# Access_Control_Passive_Splitter.net
KiCad netlist of a schematic drawn in EasyEDA Pro
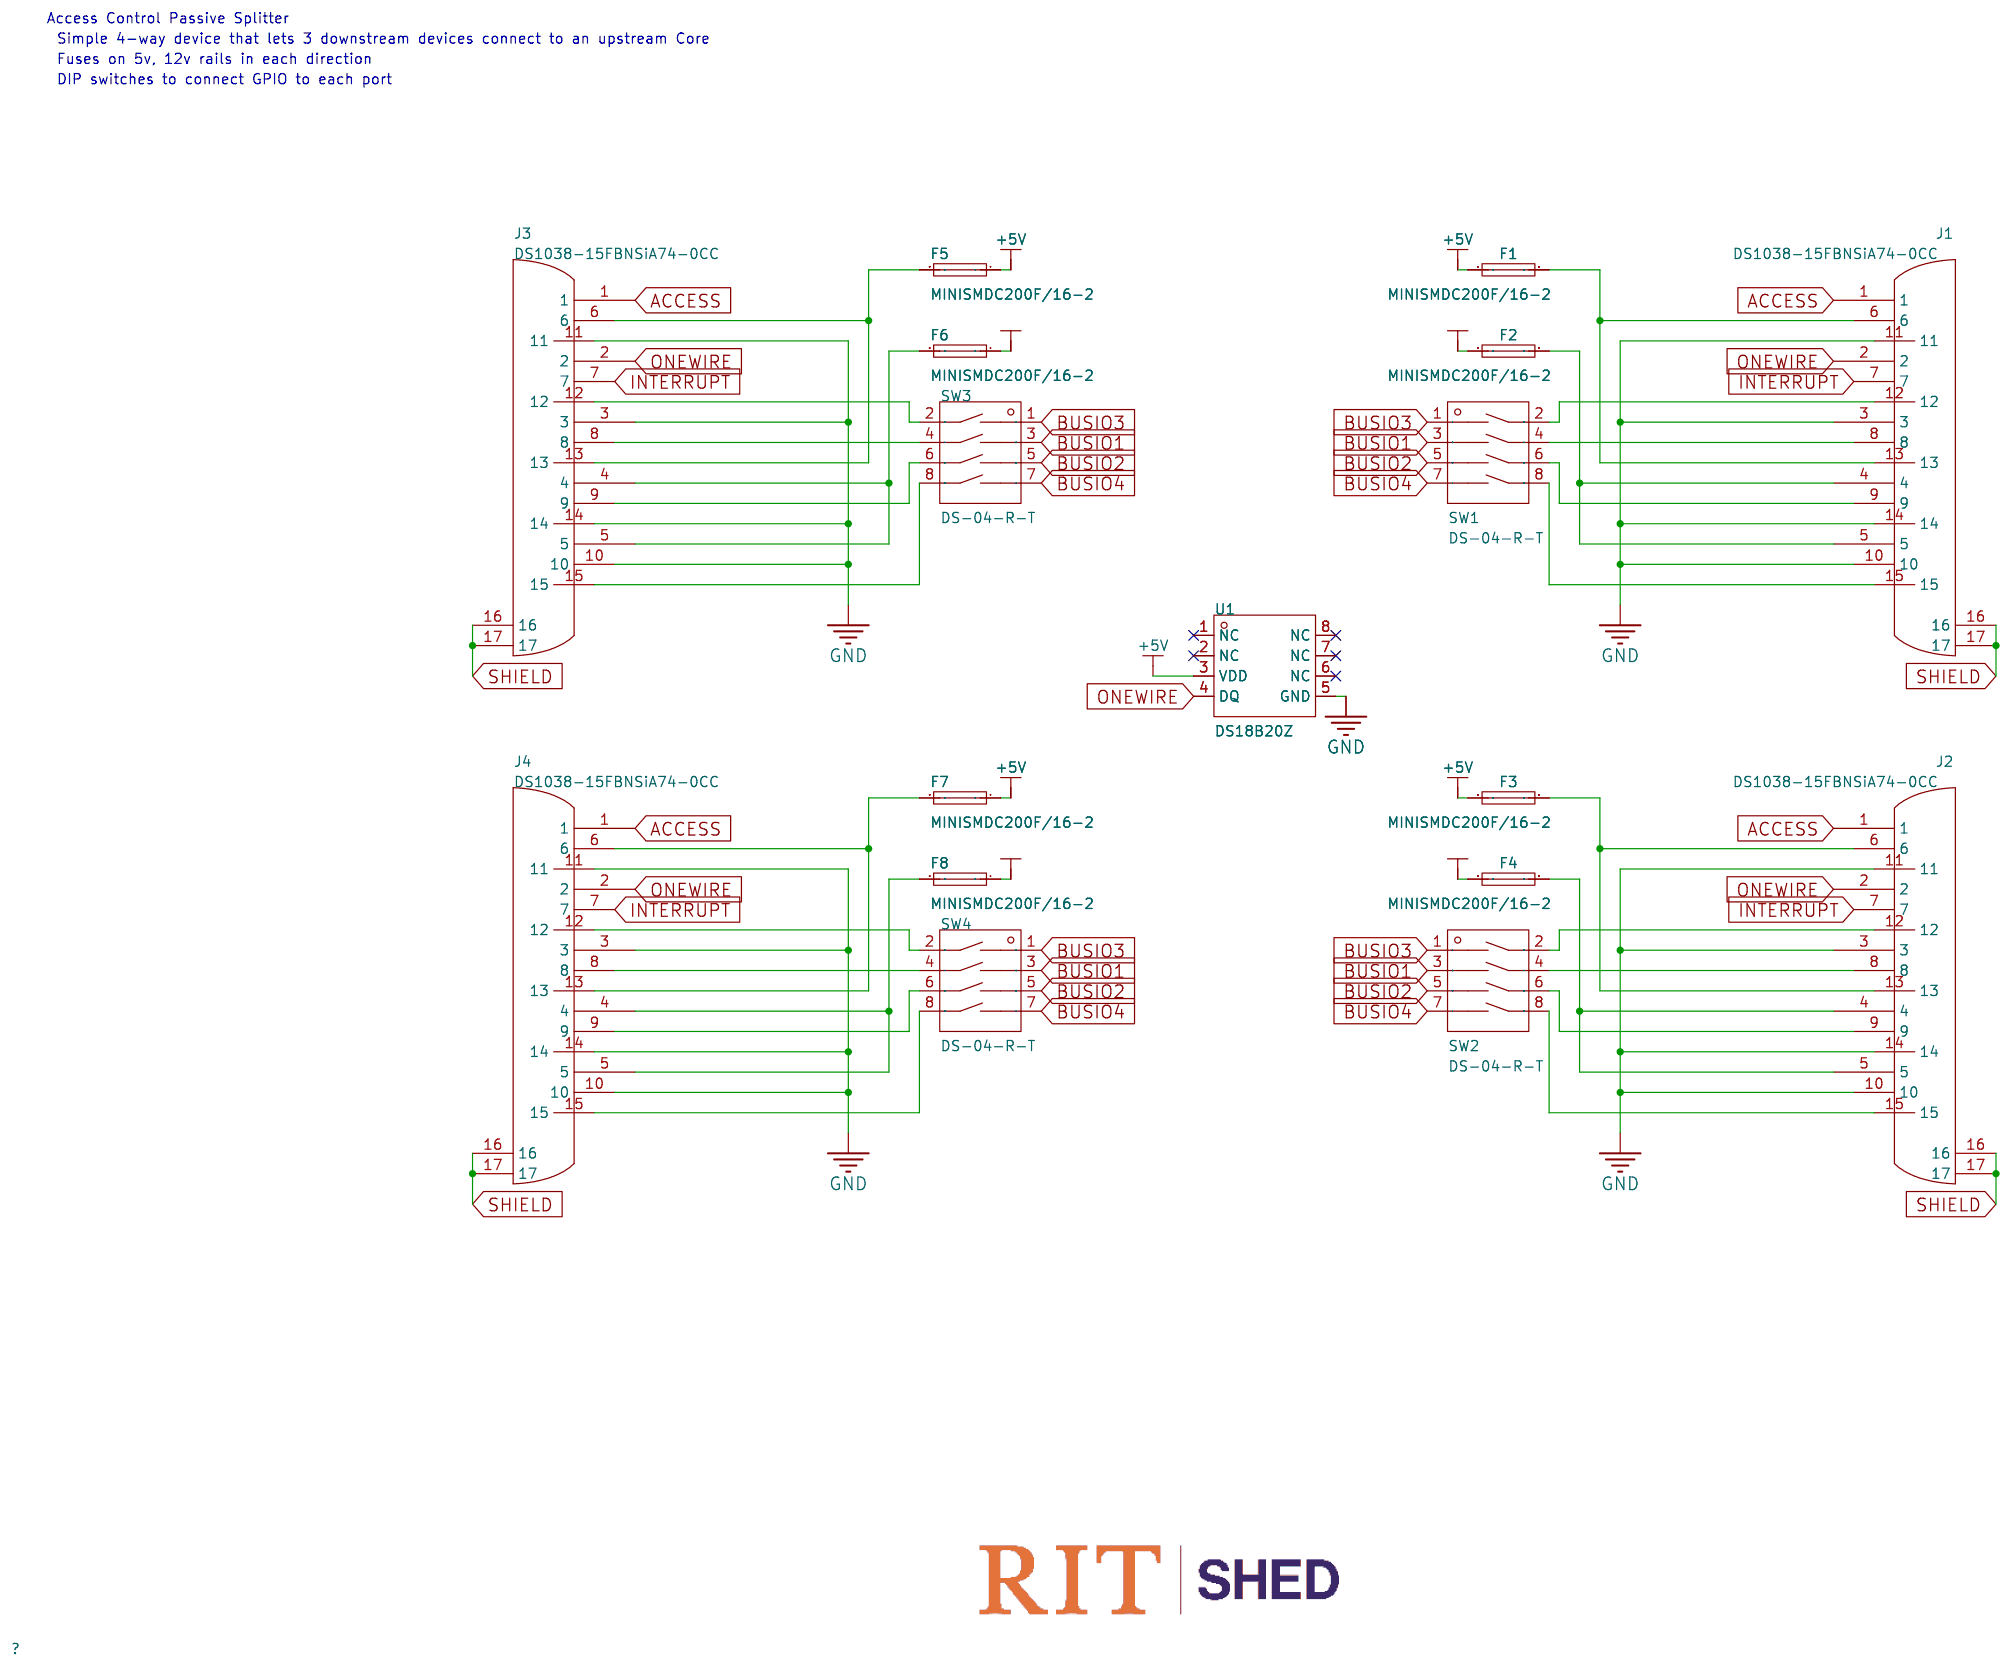
[diagram p0: schematic sheet]

(export (version "E")
  (design (tool "Eeschema 10.0.6"))
  (components
    (comp (ref "F1")
      (value "MINISMDC200F/16-2")
      (footprint "easyedapro:R1812")
      (fields (field (name "Manufacturer") "Littelfuse(美国力特)"))
      (libsource (lib "easyedapro") (part "MINISMDC200F/16-2"))
    )
    (comp (ref "F2")
      (value "MINISMDC200F/16-2")
      (footprint "easyedapro:R1812")
      (fields (field (name "Manufacturer") "Littelfuse(美国力特)"))
      (libsource (lib "easyedapro") (part "MINISMDC200F/16-2"))
    )
    (comp (ref "F3")
      (value "MINISMDC200F/16-2")
      (footprint "easyedapro:R1812")
      (fields (field (name "Manufacturer") "Littelfuse(美国力特)"))
      (libsource (lib "easyedapro") (part "MINISMDC200F/16-2"))
    )
    (comp (ref "F4")
      (value "MINISMDC200F/16-2")
      (footprint "easyedapro:R1812")
      (fields (field (name "Manufacturer") "Littelfuse(美国力特)"))
      (libsource (lib "easyedapro") (part "MINISMDC200F/16-2"))
    )
    (comp (ref "F5")
      (value "MINISMDC200F/16-2")
      (footprint "easyedapro:R1812")
      (fields (field (name "Manufacturer") "Littelfuse(美国力特)"))
      (libsource (lib "easyedapro") (part "MINISMDC200F/16-2"))
    )
    (comp (ref "F6")
      (value "MINISMDC200F/16-2")
      (footprint "easyedapro:R1812")
      (fields (field (name "Manufacturer") "Littelfuse(美国力特)"))
      (libsource (lib "easyedapro") (part "MINISMDC200F/16-2"))
    )
    (comp (ref "F7")
      (value "MINISMDC200F/16-2")
      (footprint "easyedapro:R1812")
      (fields (field (name "Manufacturer") "Littelfuse(美国力特)"))
      (libsource (lib "easyedapro") (part "MINISMDC200F/16-2"))
    )
    (comp (ref "F8")
      (value "MINISMDC200F/16-2")
      (footprint "easyedapro:R1812")
      (fields (field (name "Manufacturer") "Littelfuse(美国力特)"))
      (libsource (lib "easyedapro") (part "MINISMDC200F/16-2"))
    )
    (comp (ref "J1")
      (value "DS1038-15FBNSiA74-0CC")
      (footprint "easyedapro:DSUB-TH_DS1038-15FBNSIA74-0CC")
      (fields (field (name "Manufacturer") "CONNFLY"))
      (libsource (lib "easyedapro") (part "DS1038-15FBNSIA74-0CC"))
    )
    (comp (ref "J2")
      (value "DS1038-15FBNSiA74-0CC")
      (footprint "easyedapro:DSUB-TH_DS1038-15FBNSIA74-0CC")
      (fields (field (name "Manufacturer") "CONNFLY"))
      (libsource (lib "easyedapro") (part "DS1038-15FBNSIA74-0CC"))
    )
    (comp (ref "J3")
      (value "DS1038-15FBNSiA74-0CC")
      (footprint "easyedapro:DSUB-TH_DS1038-15FBNSIA74-0CC")
      (fields (field (name "Manufacturer") "CONNFLY"))
      (libsource (lib "easyedapro") (part "DS1038-15FBNSIA74-0CC"))
    )
    (comp (ref "J4")
      (value "DS1038-15FBNSiA74-0CC")
      (footprint "easyedapro:DSUB-TH_DS1038-15FBNSIA74-0CC")
      (fields (field (name "Manufacturer") "CONNFLY"))
      (libsource (lib "easyedapro") (part "DS1038-15FBNSIA74-0CC"))
    )
    (comp (ref "SW1")
      (value "DS-04-R-T")
      (footprint "easyedapro:SW-TH_8P-L11.6-W9.9-P2.54_WT11-DS-04RR")
      (fields (field (name "Manufacturer") "康深"))
      (libsource (lib "easyedapro") (part "DS-04-R-T"))
    )
    (comp (ref "SW2")
      (value "DS-04-R-T")
      (footprint "easyedapro:SW-TH_8P-L11.6-W9.9-P2.54_WT11-DS-04RR")
      (fields (field (name "Manufacturer") "康深"))
      (libsource (lib "easyedapro") (part "DS-04-R-T"))
    )
    (comp (ref "SW3")
      (value "DS-04-R-T")
      (footprint "easyedapro:SW-TH_8P-L11.6-W9.9-P2.54_WT11-DS-04RR")
      (fields (field (name "Manufacturer") "康深"))
      (libsource (lib "easyedapro") (part "DS-04-R-T"))
    )
    (comp (ref "SW4")
      (value "DS-04-R-T")
      (footprint "easyedapro:SW-TH_8P-L11.6-W9.9-P2.54_WT11-DS-04RR")
      (fields (field (name "Manufacturer") "康深"))
      (libsource (lib "easyedapro") (part "DS-04-R-T"))
    )
    (comp (ref "U1")
      (value "DS18B20Z")
      (footprint "easyedapro:SOP-8_L4.9-W3.9-P1.27-LS6.0-BL")
      (description "Resolution:±0.4°C Resolution:±0.4°C Supply Voltage:2.5V~5.5V Supply Voltage:2.5V~5.5V")
      (fields (field (name "Manufacturer") "UMW(友台半导体)"))
      (libsource (lib "easyedapro") (part "DS18B20Z"))
    )
  )
  (nets
    (net (code "1") (name "+5V") (class "Default")
      (node (ref "F1") (pin "1") (pinfunction "1_1") (pintype "input"))
      (node (ref "F3") (pin "1") (pinfunction "1_1") (pintype "input"))
      (node (ref "F5") (pin "1") (pinfunction "1_1") (pintype "input"))
      (node (ref "F7") (pin "1") (pinfunction "1_1") (pintype "input"))
      (node (ref "U1") (pin "3") (pinfunction "VDD_3") (pintype "unspecified"))
    )
    (net (code "2") (name "+12V") (class "Default")
      (node (ref "F2") (pin "1") (pinfunction "1_1") (pintype "input"))
      (node (ref "F4") (pin "1") (pinfunction "1_1") (pintype "input"))
      (node (ref "F6") (pin "1") (pinfunction "1_1") (pintype "input"))
      (node (ref "F8") (pin "1") (pinfunction "1_1") (pintype "input"))
    )
    (net (code "3") (name "ACCESS") (class "Default")
      (node (ref "J1") (pin "1") (pinfunction "1_1") (pintype "unspecified"))
      (node (ref "J2") (pin "1") (pinfunction "1_1") (pintype "unspecified"))
      (node (ref "J3") (pin "1") (pinfunction "1_1") (pintype "unspecified"))
      (node (ref "J4") (pin "1") (pinfunction "1_1") (pintype "unspecified"))
    )
    (net (code "4") (name "BUSIO1") (class "Default")
      (node (ref "SW1") (pin "3") (pinfunction "3_3") (pintype "unspecified"))
      (node (ref "SW2") (pin "3") (pinfunction "3_3") (pintype "unspecified"))
      (node (ref "SW3") (pin "3") (pinfunction "3_3") (pintype "unspecified"))
      (node (ref "SW4") (pin "3") (pinfunction "3_3") (pintype "unspecified"))
    )
    (net (code "5") (name "BUSIO2") (class "Default")
      (node (ref "SW1") (pin "5") (pinfunction "5_5") (pintype "unspecified"))
      (node (ref "SW2") (pin "5") (pinfunction "5_5") (pintype "unspecified"))
      (node (ref "SW3") (pin "5") (pinfunction "5_5") (pintype "unspecified"))
      (node (ref "SW4") (pin "5") (pinfunction "5_5") (pintype "unspecified"))
    )
    (net (code "6") (name "BUSIO3") (class "Default")
      (node (ref "SW1") (pin "1") (pinfunction "1_1") (pintype "unspecified"))
      (node (ref "SW2") (pin "1") (pinfunction "1_1") (pintype "unspecified"))
      (node (ref "SW3") (pin "1") (pinfunction "1_1") (pintype "unspecified"))
      (node (ref "SW4") (pin "1") (pinfunction "1_1") (pintype "unspecified"))
    )
    (net (code "7") (name "BUSIO4") (class "Default")
      (node (ref "SW1") (pin "7") (pinfunction "7_7") (pintype "unspecified"))
      (node (ref "SW2") (pin "7") (pinfunction "7_7") (pintype "unspecified"))
      (node (ref "SW3") (pin "7") (pinfunction "7_7") (pintype "unspecified"))
      (node (ref "SW4") (pin "7") (pinfunction "7_7") (pintype "unspecified"))
    )
    (net (code "8") (name "GND") (class "Default")
      (node (ref "J1") (pin "10") (pinfunction "10_10") (pintype "unspecified"))
      (node (ref "J1") (pin "11") (pinfunction "11_11") (pintype "unspecified"))
      (node (ref "J1") (pin "14") (pinfunction "14_14") (pintype "unspecified"))
      (node (ref "J1") (pin "3") (pinfunction "3_3") (pintype "unspecified"))
      (node (ref "J2") (pin "10") (pinfunction "10_10") (pintype "unspecified"))
      (node (ref "J2") (pin "11") (pinfunction "11_11") (pintype "unspecified"))
      (node (ref "J2") (pin "14") (pinfunction "14_14") (pintype "unspecified"))
      (node (ref "J2") (pin "3") (pinfunction "3_3") (pintype "unspecified"))
      (node (ref "J3") (pin "10") (pinfunction "10_10") (pintype "unspecified"))
      (node (ref "J3") (pin "11") (pinfunction "11_11") (pintype "unspecified"))
      (node (ref "J3") (pin "14") (pinfunction "14_14") (pintype "unspecified"))
      (node (ref "J3") (pin "3") (pinfunction "3_3") (pintype "unspecified"))
      (node (ref "J4") (pin "10") (pinfunction "10_10") (pintype "unspecified"))
      (node (ref "J4") (pin "11") (pinfunction "11_11") (pintype "unspecified"))
      (node (ref "J4") (pin "14") (pinfunction "14_14") (pintype "unspecified"))
      (node (ref "J4") (pin "3") (pinfunction "3_3") (pintype "unspecified"))
      (node (ref "U1") (pin "5") (pinfunction "GND_5") (pintype "unspecified"))
    )
    (net (code "9") (name "INTERRUPT") (class "Default")
      (node (ref "J1") (pin "7") (pinfunction "7_7") (pintype "unspecified"))
      (node (ref "J2") (pin "7") (pinfunction "7_7") (pintype "unspecified"))
      (node (ref "J3") (pin "7") (pinfunction "7_7") (pintype "unspecified"))
      (node (ref "J4") (pin "7") (pinfunction "7_7") (pintype "unspecified"))
    )
    (net (code "10") (name "Net-(F1-Pad2)") (class "Default")
      (node (ref "F1") (pin "2") (pinfunction "2_2") (pintype "input"))
      (node (ref "J1") (pin "13") (pinfunction "13_13") (pintype "unspecified"))
      (node (ref "J1") (pin "6") (pinfunction "6_6") (pintype "unspecified"))
    )
    (net (code "11") (name "Net-(F2-Pad2)") (class "Default")
      (node (ref "F2") (pin "2") (pinfunction "2_2") (pintype "input"))
      (node (ref "J1") (pin "4") (pinfunction "4_4") (pintype "unspecified"))
      (node (ref "J1") (pin "5") (pinfunction "5_5") (pintype "unspecified"))
    )
    (net (code "12") (name "Net-(F3-Pad2)") (class "Default")
      (node (ref "F3") (pin "2") (pinfunction "2_2") (pintype "input"))
      (node (ref "J2") (pin "13") (pinfunction "13_13") (pintype "unspecified"))
      (node (ref "J2") (pin "6") (pinfunction "6_6") (pintype "unspecified"))
    )
    (net (code "13") (name "Net-(F4-Pad2)") (class "Default")
      (node (ref "F4") (pin "2") (pinfunction "2_2") (pintype "input"))
      (node (ref "J2") (pin "4") (pinfunction "4_4") (pintype "unspecified"))
      (node (ref "J2") (pin "5") (pinfunction "5_5") (pintype "unspecified"))
    )
    (net (code "14") (name "Net-(F5-Pad2)") (class "Default")
      (node (ref "F5") (pin "2") (pinfunction "2_2") (pintype "input"))
      (node (ref "J3") (pin "13") (pinfunction "13_13") (pintype "unspecified"))
      (node (ref "J3") (pin "6") (pinfunction "6_6") (pintype "unspecified"))
    )
    (net (code "15") (name "Net-(F6-Pad2)") (class "Default")
      (node (ref "F6") (pin "2") (pinfunction "2_2") (pintype "input"))
      (node (ref "J3") (pin "4") (pinfunction "4_4") (pintype "unspecified"))
      (node (ref "J3") (pin "5") (pinfunction "5_5") (pintype "unspecified"))
    )
    (net (code "16") (name "Net-(F7-Pad2)") (class "Default")
      (node (ref "F7") (pin "2") (pinfunction "2_2") (pintype "input"))
      (node (ref "J4") (pin "13") (pinfunction "13_13") (pintype "unspecified"))
      (node (ref "J4") (pin "6") (pinfunction "6_6") (pintype "unspecified"))
    )
    (net (code "17") (name "Net-(F8-Pad2)") (class "Default")
      (node (ref "F8") (pin "2") (pinfunction "2_2") (pintype "input"))
      (node (ref "J4") (pin "4") (pinfunction "4_4") (pintype "unspecified"))
      (node (ref "J4") (pin "5") (pinfunction "5_5") (pintype "unspecified"))
    )
    (net (code "18") (name "Net-(J1-Pad8)") (class "Default")
      (node (ref "J1") (pin "8") (pinfunction "8_8") (pintype "unspecified"))
      (node (ref "SW1") (pin "4") (pinfunction "4_4") (pintype "unspecified"))
    )
    (net (code "19") (name "Net-(J1-Pad9)") (class "Default")
      (node (ref "J1") (pin "9") (pinfunction "9_9") (pintype "unspecified"))
      (node (ref "SW1") (pin "6") (pinfunction "6_6") (pintype "unspecified"))
    )
    (net (code "20") (name "Net-(J1-Pad12)") (class "Default")
      (node (ref "J1") (pin "12") (pinfunction "12_12") (pintype "unspecified"))
      (node (ref "SW1") (pin "2") (pinfunction "2_2") (pintype "unspecified"))
    )
    (net (code "21") (name "Net-(J1-Pad15)") (class "Default")
      (node (ref "J1") (pin "15") (pinfunction "15_15") (pintype "unspecified"))
      (node (ref "SW1") (pin "8") (pinfunction "8_8") (pintype "unspecified"))
    )
    (net (code "22") (name "Net-(J2-Pad8)") (class "Default")
      (node (ref "J2") (pin "8") (pinfunction "8_8") (pintype "unspecified"))
      (node (ref "SW2") (pin "4") (pinfunction "4_4") (pintype "unspecified"))
    )
    (net (code "23") (name "Net-(J2-Pad9)") (class "Default")
      (node (ref "J2") (pin "9") (pinfunction "9_9") (pintype "unspecified"))
      (node (ref "SW2") (pin "6") (pinfunction "6_6") (pintype "unspecified"))
    )
    (net (code "24") (name "Net-(J2-Pad12)") (class "Default")
      (node (ref "J2") (pin "12") (pinfunction "12_12") (pintype "unspecified"))
      (node (ref "SW2") (pin "2") (pinfunction "2_2") (pintype "unspecified"))
    )
    (net (code "25") (name "Net-(J2-Pad15)") (class "Default")
      (node (ref "J2") (pin "15") (pinfunction "15_15") (pintype "unspecified"))
      (node (ref "SW2") (pin "8") (pinfunction "8_8") (pintype "unspecified"))
    )
    (net (code "26") (name "Net-(J3-Pad8)") (class "Default")
      (node (ref "J3") (pin "8") (pinfunction "8_8") (pintype "unspecified"))
      (node (ref "SW3") (pin "4") (pinfunction "4_4") (pintype "unspecified"))
    )
    (net (code "27") (name "Net-(J3-Pad9)") (class "Default")
      (node (ref "J3") (pin "9") (pinfunction "9_9") (pintype "unspecified"))
      (node (ref "SW3") (pin "6") (pinfunction "6_6") (pintype "unspecified"))
    )
    (net (code "28") (name "Net-(J3-Pad12)") (class "Default")
      (node (ref "J3") (pin "12") (pinfunction "12_12") (pintype "unspecified"))
      (node (ref "SW3") (pin "2") (pinfunction "2_2") (pintype "unspecified"))
    )
    (net (code "29") (name "Net-(J3-Pad15)") (class "Default")
      (node (ref "J3") (pin "15") (pinfunction "15_15") (pintype "unspecified"))
      (node (ref "SW3") (pin "8") (pinfunction "8_8") (pintype "unspecified"))
    )
    (net (code "30") (name "Net-(J4-Pad8)") (class "Default")
      (node (ref "J4") (pin "8") (pinfunction "8_8") (pintype "unspecified"))
      (node (ref "SW4") (pin "4") (pinfunction "4_4") (pintype "unspecified"))
    )
    (net (code "31") (name "Net-(J4-Pad9)") (class "Default")
      (node (ref "J4") (pin "9") (pinfunction "9_9") (pintype "unspecified"))
      (node (ref "SW4") (pin "6") (pinfunction "6_6") (pintype "unspecified"))
    )
    (net (code "32") (name "Net-(J4-Pad12)") (class "Default")
      (node (ref "J4") (pin "12") (pinfunction "12_12") (pintype "unspecified"))
      (node (ref "SW4") (pin "2") (pinfunction "2_2") (pintype "unspecified"))
    )
    (net (code "33") (name "Net-(J4-Pad15)") (class "Default")
      (node (ref "J4") (pin "15") (pinfunction "15_15") (pintype "unspecified"))
      (node (ref "SW4") (pin "8") (pinfunction "8_8") (pintype "unspecified"))
    )
    (net (code "34") (name "ONEWIRE") (class "Default")
      (node (ref "J1") (pin "2") (pinfunction "2_2") (pintype "unspecified"))
      (node (ref "J2") (pin "2") (pinfunction "2_2") (pintype "unspecified"))
      (node (ref "J3") (pin "2") (pinfunction "2_2") (pintype "unspecified"))
      (node (ref "J4") (pin "2") (pinfunction "2_2") (pintype "unspecified"))
      (node (ref "U1") (pin "4") (pinfunction "DQ_4") (pintype "unspecified"))
    )
    (net (code "35") (name "SHIELD") (class "Default")
      (node (ref "J1") (pin "16") (pinfunction "16_16") (pintype "unspecified"))
      (node (ref "J1") (pin "17") (pinfunction "17_17") (pintype "unspecified"))
      (node (ref "J2") (pin "16") (pinfunction "16_16") (pintype "unspecified"))
      (node (ref "J2") (pin "17") (pinfunction "17_17") (pintype "unspecified"))
      (node (ref "J3") (pin "16") (pinfunction "16_16") (pintype "unspecified"))
      (node (ref "J3") (pin "17") (pinfunction "17_17") (pintype "unspecified"))
      (node (ref "J4") (pin "16") (pinfunction "16_16") (pintype "unspecified"))
      (node (ref "J4") (pin "17") (pinfunction "17_17") (pintype "unspecified"))
    )
    (net (code "36") (name "unconnected-(U1-NC-Pad1)") (class "Default")
      (node (ref "U1") (pin "1") (pinfunction "NC_1") (pintype "unspecified+no_connect"))
    )
    (net (code "37") (name "unconnected-(U1-NC-Pad2)") (class "Default")
      (node (ref "U1") (pin "2") (pinfunction "NC_2") (pintype "unspecified+no_connect"))
    )
    (net (code "38") (name "unconnected-(U1-NC-Pad6)") (class "Default")
      (node (ref "U1") (pin "6") (pinfunction "NC_6") (pintype "unspecified+no_connect"))
    )
    (net (code "39") (name "unconnected-(U1-NC-Pad7)") (class "Default")
      (node (ref "U1") (pin "7") (pinfunction "NC_7") (pintype "unspecified+no_connect"))
    )
    (net (code "40") (name "unconnected-(U1-NC-Pad8)") (class "Default")
      (node (ref "U1") (pin "8") (pinfunction "NC_8") (pintype "unspecified+no_connect"))
    )
  )
)
